# glove-unit.net
KiCad netlist of a schematic drawn in EAGLE
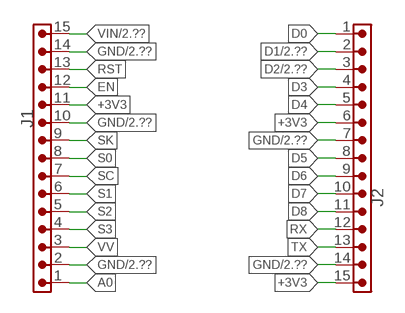
[diagram p0: schematic, sheet 1]
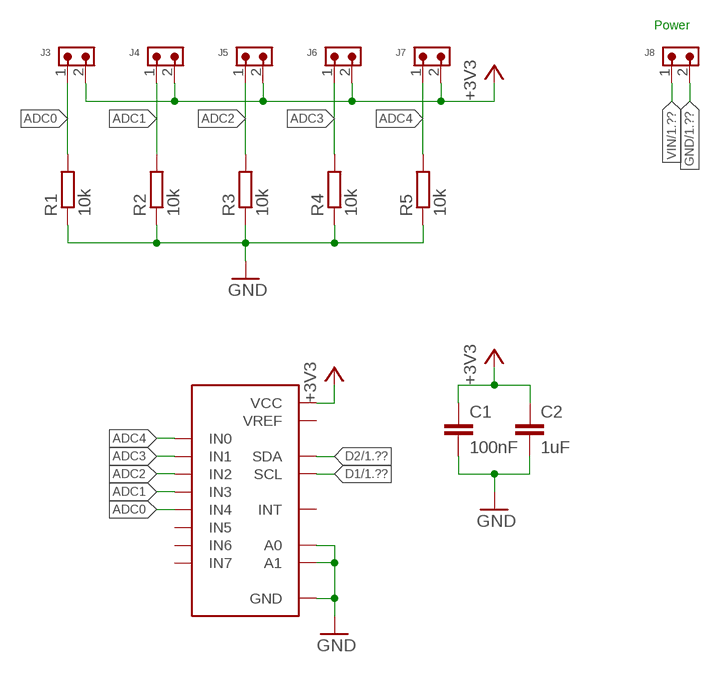
[diagram p1: schematic, sheet 2]

(export (version "E")
  (design (tool "Eeschema 10.0.6"))
  (components
    (comp (ref "C1")
      (value "100nF")
      (footprint "eagle-import:C0603")
      (libsource (lib "eagle-import") (part "CC0603"))
    )
    (comp (ref "C2")
      (value "1uF")
      (footprint "eagle-import:C0603")
      (libsource (lib "eagle-import") (part "CC0603"))
    )
    (comp (ref "J3")
      (value "6130XX11121_61300211121")
      (footprint "eagle-import:61300211121")
      (libsource (lib "eagle-import") (part "6130XX11121_61300211121"))
    )
    (comp (ref "J4")
      (value "6130XX11121_61300211121")
      (footprint "eagle-import:61300211121")
      (libsource (lib "eagle-import") (part "6130XX11121_61300211121"))
    )
    (comp (ref "J5")
      (value "6130XX11121_61300211121")
      (footprint "eagle-import:61300211121")
      (libsource (lib "eagle-import") (part "6130XX11121_61300211121"))
    )
    (comp (ref "J6")
      (value "6130XX11121_61300211121")
      (footprint "eagle-import:61300211121")
      (libsource (lib "eagle-import") (part "6130XX11121_61300211121"))
    )
    (comp (ref "J7")
      (value "6130XX11121_61300211121")
      (footprint "eagle-import:61300211121")
      (libsource (lib "eagle-import") (part "6130XX11121_61300211121"))
    )
    (comp (ref "J8")
      (value "6130XX11121_61300211121")
      (footprint "eagle-import:61300211121")
      (libsource (lib "eagle-import") (part "6130XX11121_61300211121"))
    )
    (comp (ref "R1")
      (value "10k")
      (footprint "eagle-import:R0805")
      (libsource (lib "eagle-import") (part "R"))
    )
    (comp (ref "R2")
      (value "10k")
      (footprint "eagle-import:R0805")
      (libsource (lib "eagle-import") (part "R"))
    )
    (comp (ref "R3")
      (value "10k")
      (footprint "eagle-import:R0805")
      (libsource (lib "eagle-import") (part "R"))
    )
    (comp (ref "R4")
      (value "10k")
      (footprint "eagle-import:R0805")
      (libsource (lib "eagle-import") (part "R"))
    )
    (comp (ref "R5")
      (value "10k")
      (footprint "eagle-import:R0805")
      (libsource (lib "eagle-import") (part "R"))
    )
    (comp (ref "U$1")
      (value "ADC128D818")
      (footprint "eagle-import:TSSOP-16")
      (libsource (lib "eagle-import") (part "ADC128D818"))
    )
    (comp (ref "J1")
      (value "6130XX11121_61301511121")
      (footprint "eagle-import:61301511121")
      (libsource (lib "eagle-import") (part "6130XX11121_61301511121"))
    )
    (comp (ref "J2")
      (value "6130XX11121_61301511121")
      (footprint "eagle-import:61301511121")
      (libsource (lib "eagle-import") (part "6130XX11121_61301511121"))
    )
  )
  (nets
    (net (code "1") (name "+3V3") (class "Default")
      (node (ref "C1") (pin "1") (pinfunction "1_1") (pintype "passive"))
      (node (ref "C2") (pin "1") (pinfunction "1_1") (pintype "passive"))
      (node (ref "J1") (pin "11") (pinfunction "11_11") (pintype "passive"))
      (node (ref "J2") (pin "15") (pinfunction "15_15") (pintype "passive"))
      (node (ref "J2") (pin "6") (pinfunction "6_6") (pintype "passive"))
      (node (ref "J3") (pin "2") (pinfunction "2_2") (pintype "passive"))
      (node (ref "J4") (pin "2") (pinfunction "2_2") (pintype "passive"))
      (node (ref "J5") (pin "2") (pinfunction "2_2") (pintype "passive"))
      (node (ref "J6") (pin "2") (pinfunction "2_2") (pintype "passive"))
      (node (ref "J7") (pin "2") (pinfunction "2_2") (pintype "passive"))
      (node (ref "U$1") (pin "5") (pinfunction "VCC_5") (pintype "bidirectional"))
    )
    (net (code "2") (name "A0") (class "Default")
      (node (ref "J1") (pin "1") (pinfunction "1_1") (pintype "passive"))
    )
    (net (code "3") (name "ADC0") (class "Default")
      (node (ref "J3") (pin "1") (pinfunction "1_1") (pintype "passive"))
      (node (ref "R1") (pin "2") (pinfunction "2_2") (pintype "passive"))
      (node (ref "U$1") (pin "12") (pinfunction "IN4_12") (pintype "bidirectional"))
    )
    (net (code "4") (name "ADC1") (class "Default")
      (node (ref "J4") (pin "1") (pinfunction "1_1") (pintype "passive"))
      (node (ref "R2") (pin "2") (pinfunction "2_2") (pintype "passive"))
      (node (ref "U$1") (pin "13") (pinfunction "IN3_13") (pintype "bidirectional"))
    )
    (net (code "5") (name "ADC2") (class "Default")
      (node (ref "J5") (pin "1") (pinfunction "1_1") (pintype "passive"))
      (node (ref "R3") (pin "2") (pinfunction "2_2") (pintype "passive"))
      (node (ref "U$1") (pin "14") (pinfunction "IN2_14") (pintype "bidirectional"))
    )
    (net (code "6") (name "ADC3") (class "Default")
      (node (ref "J6") (pin "1") (pinfunction "1_1") (pintype "passive"))
      (node (ref "R4") (pin "2") (pinfunction "2_2") (pintype "passive"))
      (node (ref "U$1") (pin "15") (pinfunction "IN1_15") (pintype "bidirectional"))
    )
    (net (code "7") (name "ADC4") (class "Default")
      (node (ref "J7") (pin "1") (pinfunction "1_1") (pintype "passive"))
      (node (ref "R5") (pin "2") (pinfunction "2_2") (pintype "passive"))
      (node (ref "U$1") (pin "16") (pinfunction "IN0_16") (pintype "bidirectional"))
    )
    (net (code "8") (name "D0") (class "Default")
      (node (ref "J2") (pin "1") (pinfunction "1_1") (pintype "passive"))
    )
    (net (code "9") (name "D1") (class "Default")
      (node (ref "J2") (pin "2") (pinfunction "2_2") (pintype "passive"))
      (node (ref "U$1") (pin "3") (pinfunction "SCL_3") (pintype "bidirectional"))
    )
    (net (code "10") (name "D2") (class "Default")
      (node (ref "J2") (pin "3") (pinfunction "3_3") (pintype "passive"))
      (node (ref "U$1") (pin "2") (pinfunction "SDA_2") (pintype "bidirectional"))
    )
    (net (code "11") (name "D3") (class "Default")
      (node (ref "J2") (pin "4") (pinfunction "4_4") (pintype "passive"))
    )
    (net (code "12") (name "D4") (class "Default")
      (node (ref "J2") (pin "5") (pinfunction "5_5") (pintype "passive"))
    )
    (net (code "13") (name "D5") (class "Default")
      (node (ref "J2") (pin "8") (pinfunction "8_8") (pintype "passive"))
    )
    (net (code "14") (name "D6") (class "Default")
      (node (ref "J2") (pin "9") (pinfunction "9_9") (pintype "passive"))
    )
    (net (code "15") (name "D7") (class "Default")
      (node (ref "J2") (pin "10") (pinfunction "10_10") (pintype "passive"))
    )
    (net (code "16") (name "D8") (class "Default")
      (node (ref "J2") (pin "11") (pinfunction "11_11") (pintype "passive"))
    )
    (net (code "17") (name "EN") (class "Default")
      (node (ref "J1") (pin "12") (pinfunction "12_12") (pintype "passive"))
    )
    (net (code "18") (name "GND") (class "Default")
      (node (ref "C1") (pin "2") (pinfunction "2_2") (pintype "passive"))
      (node (ref "C2") (pin "2") (pinfunction "2_2") (pintype "passive"))
      (node (ref "J1") (pin "10") (pinfunction "10_10") (pintype "passive"))
      (node (ref "J1") (pin "14") (pinfunction "14_14") (pintype "passive"))
      (node (ref "J1") (pin "2") (pinfunction "2_2") (pintype "passive"))
      (node (ref "J2") (pin "14") (pinfunction "14_14") (pintype "passive"))
      (node (ref "J2") (pin "7") (pinfunction "7_7") (pintype "passive"))
      (node (ref "J8") (pin "2") (pinfunction "2_2") (pintype "passive"))
      (node (ref "R1") (pin "1") (pinfunction "1_1") (pintype "passive"))
      (node (ref "R2") (pin "1") (pinfunction "1_1") (pintype "passive"))
      (node (ref "R3") (pin "1") (pinfunction "1_1") (pintype "passive"))
      (node (ref "R4") (pin "1") (pinfunction "1_1") (pintype "passive"))
      (node (ref "R5") (pin "1") (pinfunction "1_1") (pintype "passive"))
      (node (ref "U$1") (pin "4") (pinfunction "GND_4") (pintype "bidirectional"))
      (node (ref "U$1") (pin "7") (pinfunction "A0_7") (pintype "bidirectional"))
      (node (ref "U$1") (pin "8") (pinfunction "A1_8") (pintype "bidirectional"))
    )
    (net (code "19") (name "RST") (class "Default")
      (node (ref "J1") (pin "13") (pinfunction "13_13") (pintype "passive"))
    )
    (net (code "20") (name "RX") (class "Default")
      (node (ref "J2") (pin "12") (pinfunction "12_12") (pintype "passive"))
    )
    (net (code "21") (name "S0") (class "Default")
      (node (ref "J1") (pin "8") (pinfunction "8_8") (pintype "passive"))
    )
    (net (code "22") (name "S1") (class "Default")
      (node (ref "J1") (pin "6") (pinfunction "6_6") (pintype "passive"))
    )
    (net (code "23") (name "S2") (class "Default")
      (node (ref "J1") (pin "5") (pinfunction "5_5") (pintype "passive"))
    )
    (net (code "24") (name "S3") (class "Default")
      (node (ref "J1") (pin "4") (pinfunction "4_4") (pintype "passive"))
    )
    (net (code "25") (name "SC") (class "Default")
      (node (ref "J1") (pin "7") (pinfunction "7_7") (pintype "passive"))
    )
    (net (code "26") (name "SK") (class "Default")
      (node (ref "J1") (pin "9") (pinfunction "9_9") (pintype "passive"))
    )
    (net (code "27") (name "TX") (class "Default")
      (node (ref "J2") (pin "13") (pinfunction "13_13") (pintype "passive"))
    )
    (net (code "28") (name "VIN") (class "Default")
      (node (ref "J1") (pin "15") (pinfunction "15_15") (pintype "passive"))
      (node (ref "J8") (pin "1") (pinfunction "1_1") (pintype "passive"))
    )
    (net (code "29") (name "VV") (class "Default")
      (node (ref "J1") (pin "3") (pinfunction "3_3") (pintype "passive"))
    )
    (net (code "30") (name "unconnected-(U$1-IN5-Pad11)") (class "Default")
      (node (ref "U$1") (pin "11") (pinfunction "IN5_11") (pintype "bidirectional"))
    )
    (net (code "31") (name "unconnected-(U$1-IN6-Pad10)") (class "Default")
      (node (ref "U$1") (pin "10") (pinfunction "IN6_10") (pintype "bidirectional"))
    )
    (net (code "32") (name "unconnected-(U$1-IN7-Pad9)") (class "Default")
      (node (ref "U$1") (pin "9") (pinfunction "IN7_9") (pintype "bidirectional"))
    )
    (net (code "33") (name "unconnected-(U$1-INT-Pad6)") (class "Default")
      (node (ref "U$1") (pin "6") (pinfunction "INT_6") (pintype "bidirectional"))
    )
    (net (code "34") (name "unconnected-(U$1-VREF-Pad1)") (class "Default")
      (node (ref "U$1") (pin "1") (pinfunction "VREF_1") (pintype "bidirectional"))
    )
  )
)
